# pot_board_2.net
KiCad netlist of a schematic drawn in EAGLE
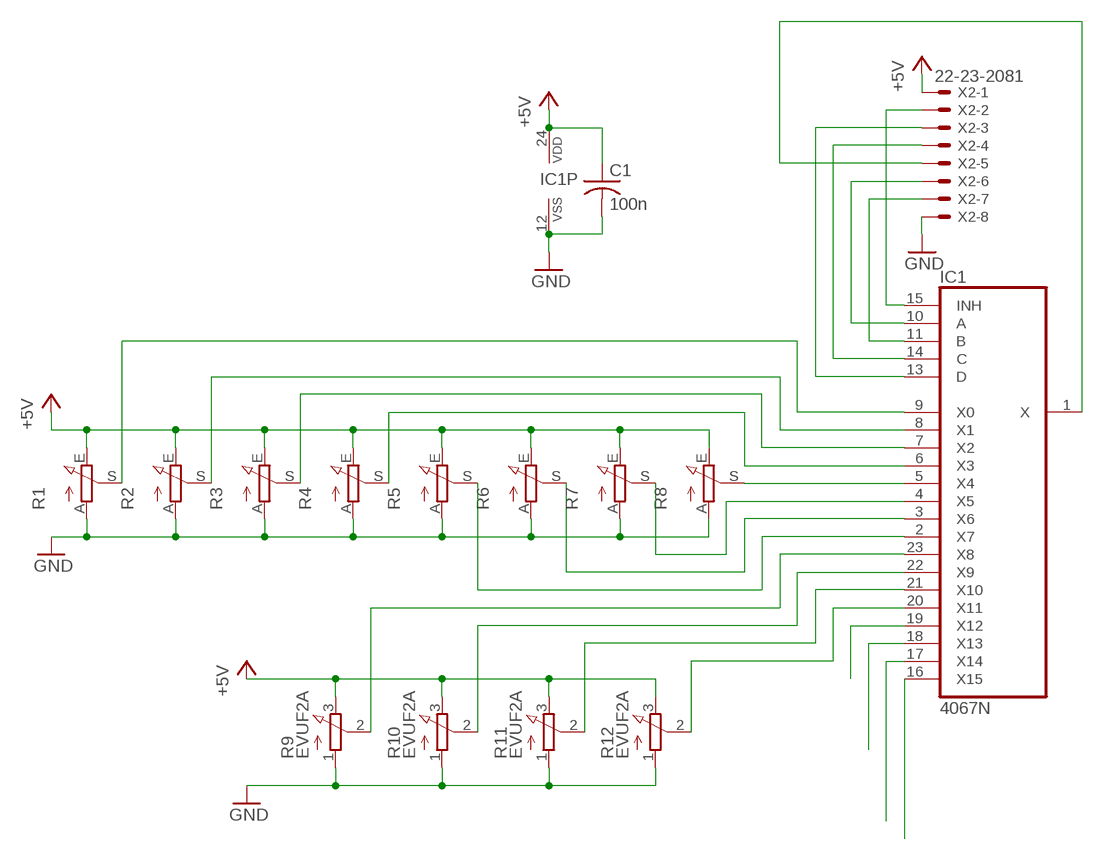
[diagram p0: schematic, sheet 1]

(export (version "E")
  (design (tool "Eeschema 10.0.6"))
  (components
    (comp (ref "C1")
      (value "100n")
      (footprint "eagle-import:C025-024X044")
      (libsource (lib "eagle-import") (part "C-US025-024X044"))
    )
    (comp (ref "IC1")
      (value "4067N")
      (footprint "eagle-import:DIL24-6")
      (libsource (lib "eagle-import") (part "4067N"))
    )
    (comp (ref "R1")
      (value "3RP/1610N45MM-SLIDE")
      (footprint "eagle-import:ST15")
      (libsource (lib "eagle-import") (part "3RP/1610N45MM-SLIDE"))
    )
    (comp (ref "R2")
      (value "3RP/1610N45MM-SLIDE")
      (footprint "eagle-import:ST15")
      (libsource (lib "eagle-import") (part "3RP/1610N45MM-SLIDE"))
    )
    (comp (ref "R3")
      (value "3RP/1610N45MM-SLIDE")
      (footprint "eagle-import:ST15")
      (libsource (lib "eagle-import") (part "3RP/1610N45MM-SLIDE"))
    )
    (comp (ref "R4")
      (value "3RP/1610N45MM-SLIDE")
      (footprint "eagle-import:ST15")
      (libsource (lib "eagle-import") (part "3RP/1610N45MM-SLIDE"))
    )
    (comp (ref "R5")
      (value "3RP/1610N45MM-SLIDE")
      (footprint "eagle-import:ST15")
      (libsource (lib "eagle-import") (part "3RP/1610N45MM-SLIDE"))
    )
    (comp (ref "R6")
      (value "3RP/1610N45MM-SLIDE")
      (footprint "eagle-import:ST15")
      (libsource (lib "eagle-import") (part "3RP/1610N45MM-SLIDE"))
    )
    (comp (ref "R7")
      (value "3RP/1610N45MM-SLIDE")
      (footprint "eagle-import:ST15")
      (libsource (lib "eagle-import") (part "3RP/1610N45MM-SLIDE"))
    )
    (comp (ref "R8")
      (value "3RP/1610N45MM-SLIDE")
      (footprint "eagle-import:ST15")
      (libsource (lib "eagle-import") (part "3RP/1610N45MM-SLIDE"))
    )
    (comp (ref "R9")
      (value "EVUF2A")
      (footprint "eagle-import:EVUF")
      (libsource (lib "eagle-import") (part "EVUAF2"))
    )
    (comp (ref "R10")
      (value "EVUF2A")
      (footprint "eagle-import:EVUF")
      (libsource (lib "eagle-import") (part "EVUAF2"))
    )
    (comp (ref "R11")
      (value "EVUF2A")
      (footprint "eagle-import:EVUF")
      (libsource (lib "eagle-import") (part "EVUAF2"))
    )
    (comp (ref "R12")
      (value "EVUF2A")
      (footprint "eagle-import:EVUF")
      (libsource (lib "eagle-import") (part "EVUAF2"))
    )
    (comp (ref "X2")
      (value "22-23-2081")
      (footprint "eagle-import:22-23-2081")
      (fields (field (name "MF") "MOLEX"))
      (libsource (lib "eagle-import") (part "22-23-2081"))
    )
  )
  (nets
    (net (code "1") (name "+5V") (class "Default")
      (node (ref "C1") (pin "1") (pinfunction "1_1") (pintype "passive"))
      (node (ref "IC1") (pin "24") (pinfunction "VDD_24") (pintype "power_in"))
      (node (ref "R1") (pin "E") (pinfunction "E_E") (pintype "passive"))
      (node (ref "R10") (pin "3") (pinfunction "E_3") (pintype "passive"))
      (node (ref "R11") (pin "3") (pinfunction "E_3") (pintype "passive"))
      (node (ref "R12") (pin "3") (pinfunction "E_3") (pintype "passive"))
      (node (ref "R2") (pin "E") (pinfunction "E_E") (pintype "passive"))
      (node (ref "R3") (pin "E") (pinfunction "E_E") (pintype "passive"))
      (node (ref "R4") (pin "E") (pinfunction "E_E") (pintype "passive"))
      (node (ref "R5") (pin "E") (pinfunction "E_E") (pintype "passive"))
      (node (ref "R6") (pin "E") (pinfunction "E_E") (pintype "passive"))
      (node (ref "R7") (pin "E") (pinfunction "E_E") (pintype "passive"))
      (node (ref "R8") (pin "E") (pinfunction "E_E") (pintype "passive"))
      (node (ref "R9") (pin "3") (pinfunction "E_3") (pintype "passive"))
      (node (ref "X2") (pin "1") (pinfunction "S_1") (pintype "passive"))
    )
    (net (code "2") (name "GND") (class "Default")
      (node (ref "C1") (pin "2") (pinfunction "2_2") (pintype "passive"))
      (node (ref "IC1") (pin "12") (pinfunction "VSS_12") (pintype "power_in"))
      (node (ref "R1") (pin "A") (pinfunction "A_A") (pintype "passive"))
      (node (ref "R10") (pin "1") (pinfunction "A_1") (pintype "passive"))
      (node (ref "R11") (pin "1") (pinfunction "A_1") (pintype "passive"))
      (node (ref "R12") (pin "1") (pinfunction "A_1") (pintype "passive"))
      (node (ref "R2") (pin "A") (pinfunction "A_A") (pintype "passive"))
      (node (ref "R3") (pin "A") (pinfunction "A_A") (pintype "passive"))
      (node (ref "R4") (pin "A") (pinfunction "A_A") (pintype "passive"))
      (node (ref "R5") (pin "A") (pinfunction "A_A") (pintype "passive"))
      (node (ref "R6") (pin "A") (pinfunction "A_A") (pintype "passive"))
      (node (ref "R7") (pin "A") (pinfunction "A_A") (pintype "passive"))
      (node (ref "R8") (pin "A") (pinfunction "A_A") (pintype "passive"))
      (node (ref "R9") (pin "1") (pinfunction "A_1") (pintype "passive"))
      (node (ref "X2") (pin "8") (pinfunction "S_8") (pintype "passive"))
    )
    (net (code "3") (name "Net-(IC1A-A)") (class "Default")
      (node (ref "IC1") (pin "10") (pinfunction "A_10") (pintype "input"))
      (node (ref "X2") (pin "6") (pinfunction "S_6") (pintype "passive"))
    )
    (net (code "4") (name "Net-(IC1A-B)") (class "Default")
      (node (ref "IC1") (pin "11") (pinfunction "B_11") (pintype "input"))
      (node (ref "X2") (pin "7") (pinfunction "S_7") (pintype "passive"))
    )
    (net (code "5") (name "Net-(IC1A-C)") (class "Default")
      (node (ref "IC1") (pin "14") (pinfunction "C_14") (pintype "input"))
      (node (ref "X2") (pin "4") (pinfunction "S_4") (pintype "passive"))
    )
    (net (code "6") (name "Net-(IC1A-D)") (class "Default")
      (node (ref "IC1") (pin "13") (pinfunction "D_13") (pintype "input"))
      (node (ref "X2") (pin "3") (pinfunction "S_3") (pintype "passive"))
    )
    (net (code "7") (name "Net-(IC1A-INH)") (class "Default")
      (node (ref "IC1") (pin "15") (pinfunction "INH_15") (pintype "input"))
      (node (ref "X2") (pin "2") (pinfunction "S_2") (pintype "passive"))
    )
    (net (code "8") (name "Net-(IC1A-X)") (class "Default")
      (node (ref "IC1") (pin "1") (pinfunction "X_1") (pintype "output"))
      (node (ref "X2") (pin "5") (pinfunction "S_5") (pintype "passive"))
    )
    (net (code "9") (name "Net-(IC1A-X0)") (class "Default")
      (node (ref "IC1") (pin "9") (pinfunction "X0_9") (pintype "input"))
      (node (ref "R1") (pin "S") (pinfunction "S_S") (pintype "passive"))
    )
    (net (code "10") (name "Net-(IC1A-X1)") (class "Default")
      (node (ref "IC1") (pin "8") (pinfunction "X1_8") (pintype "input"))
      (node (ref "R2") (pin "S") (pinfunction "S_S") (pintype "passive"))
    )
    (net (code "11") (name "Net-(IC1A-X2)") (class "Default")
      (node (ref "IC1") (pin "7") (pinfunction "X2_7") (pintype "input"))
      (node (ref "R3") (pin "S") (pinfunction "S_S") (pintype "passive"))
    )
    (net (code "12") (name "Net-(IC1A-X3)") (class "Default")
      (node (ref "IC1") (pin "6") (pinfunction "X3_6") (pintype "input"))
      (node (ref "R4") (pin "S") (pinfunction "S_S") (pintype "passive"))
    )
    (net (code "13") (name "Net-(IC1A-X4)") (class "Default")
      (node (ref "IC1") (pin "5") (pinfunction "X4_5") (pintype "input"))
      (node (ref "R8") (pin "S") (pinfunction "S_S") (pintype "passive"))
    )
    (net (code "14") (name "Net-(IC1A-X5)") (class "Default")
      (node (ref "IC1") (pin "4") (pinfunction "X5_4") (pintype "input"))
      (node (ref "R7") (pin "S") (pinfunction "S_S") (pintype "passive"))
    )
    (net (code "15") (name "Net-(IC1A-X6)") (class "Default")
      (node (ref "IC1") (pin "3") (pinfunction "X6_3") (pintype "input"))
      (node (ref "R6") (pin "S") (pinfunction "S_S") (pintype "passive"))
    )
    (net (code "16") (name "Net-(IC1A-X7)") (class "Default")
      (node (ref "IC1") (pin "2") (pinfunction "X7_2") (pintype "input"))
      (node (ref "R5") (pin "S") (pinfunction "S_S") (pintype "passive"))
    )
    (net (code "17") (name "Net-(IC1A-X8)") (class "Default")
      (node (ref "IC1") (pin "23") (pinfunction "X8_23") (pintype "input"))
      (node (ref "R9") (pin "2") (pinfunction "S_2") (pintype "passive"))
    )
    (net (code "18") (name "Net-(IC1A-X9)") (class "Default")
      (node (ref "IC1") (pin "22") (pinfunction "X9_22") (pintype "input"))
      (node (ref "R10") (pin "2") (pinfunction "S_2") (pintype "passive"))
    )
    (net (code "19") (name "Net-(IC1A-X10)") (class "Default")
      (node (ref "IC1") (pin "21") (pinfunction "X10_21") (pintype "input"))
      (node (ref "R11") (pin "2") (pinfunction "S_2") (pintype "passive"))
    )
    (net (code "20") (name "Net-(IC1A-X11)") (class "Default")
      (node (ref "IC1") (pin "20") (pinfunction "X11_20") (pintype "input"))
      (node (ref "R12") (pin "2") (pinfunction "S_2") (pintype "passive"))
    )
    (net (code "21") (name "unconnected-(IC1A-X12-Pad19)") (class "Default")
      (node (ref "IC1") (pin "19") (pinfunction "X12_19") (pintype "input"))
    )
    (net (code "22") (name "unconnected-(IC1A-X13-Pad18)") (class "Default")
      (node (ref "IC1") (pin "18") (pinfunction "X13_18") (pintype "input"))
    )
    (net (code "23") (name "unconnected-(IC1A-X14-Pad17)") (class "Default")
      (node (ref "IC1") (pin "17") (pinfunction "X14_17") (pintype "input"))
    )
    (net (code "24") (name "unconnected-(IC1A-X15-Pad16)") (class "Default")
      (node (ref "IC1") (pin "16") (pinfunction "X15_16") (pintype "input"))
    )
  )
)
